# untitled.net
KiCad netlist of a schematic drawn in EAGLE
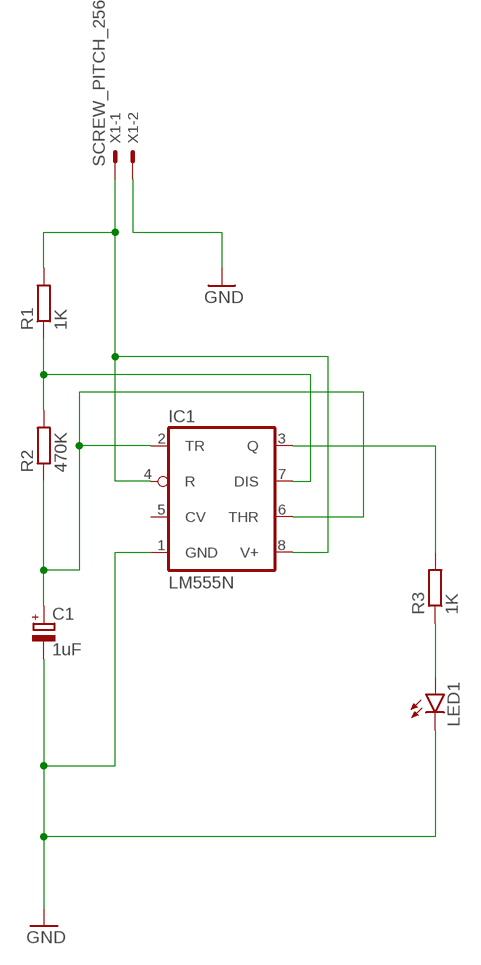
[diagram p0: schematic, sheet 1]

(export (version "E")
  (design (tool "Eeschema 10.0.6"))
  (components
    (comp (ref "C1")
      (value "1uF")
      (footprint "eagle-import:E2-5")
      (libsource (lib "eagle-import") (part "CPOL-EUE2-5"))
    )
    (comp (ref "IC1")
      (value "LM555N")
      (footprint "eagle-import:DIL08")
      (libsource (lib "eagle-import") (part "555NLM"))
    )
    (comp (ref "LED1")
      (value "LED_1206SMT1206")
      (footprint "eagle-import:1206")
      (libsource (lib "eagle-import") (part "LED_1206SMT1206"))
    )
    (comp (ref "R1")
      (value "1K")
      (footprint "eagle-import:0207_10")
      (libsource (lib "eagle-import") (part "CARBON/METAL_FILM_RESISTOR0207/10"))
    )
    (comp (ref "R2")
      (value "470K")
      (footprint "eagle-import:0207_10")
      (libsource (lib "eagle-import") (part "CARBON/METAL_FILM_RESISTOR0207/10"))
    )
    (comp (ref "R3")
      (value "1K")
      (footprint "eagle-import:0207_10")
      (libsource (lib "eagle-import") (part "CARBON/METAL_FILM_RESISTOR0207/10"))
    )
    (comp (ref "X1")
      (value "SCREW_PITCH_256")
      (footprint "eagle-import:22-23-2021")
      (fields (field (name "MF") "MOLEX") (field (name "MPN") "22-23-2021"))
      (libsource (lib "eagle-import") (part "SCREW_PITCH_256"))
    )
  )
  (nets
    (net (code "1") (name "GND") (class "Default")
      (node (ref "C1") (pin "-") (pinfunction "-_-") (pintype "passive"))
      (node (ref "IC1") (pin "1") (pinfunction "GND_1") (pintype "power_in"))
      (node (ref "LED1") (pin "C") (pinfunction "C_C") (pintype "passive"))
      (node (ref "X1") (pin "2") (pinfunction "S_2") (pintype "passive"))
    )
    (net (code "2") (name "Net-(IC1-DIS)") (class "Default")
      (node (ref "IC1") (pin "7") (pinfunction "DIS_7") (pintype "input"))
      (node (ref "R1") (pin "1") (pinfunction "1_1") (pintype "passive"))
      (node (ref "R2") (pin "2") (pinfunction "2_2") (pintype "passive"))
    )
    (net (code "3") (name "Net-(IC1-Q)") (class "Default")
      (node (ref "IC1") (pin "3") (pinfunction "Q_3") (pintype "output"))
      (node (ref "R3") (pin "2") (pinfunction "2_2") (pintype "passive"))
    )
    (net (code "4") (name "Net-(IC1-R)") (class "Default")
      (node (ref "IC1") (pin "4") (pinfunction "R_4") (pintype "input"))
      (node (ref "IC1") (pin "8") (pinfunction "V+_8") (pintype "power_in"))
      (node (ref "R1") (pin "2") (pinfunction "2_2") (pintype "passive"))
      (node (ref "X1") (pin "1") (pinfunction "S_1") (pintype "passive"))
    )
    (net (code "5") (name "Net-(IC1-THR)") (class "Default")
      (node (ref "C1") (pin "+") (pinfunction "+_+") (pintype "passive"))
      (node (ref "IC1") (pin "2") (pinfunction "TR_2") (pintype "input"))
      (node (ref "IC1") (pin "6") (pinfunction "THR_6") (pintype "input"))
      (node (ref "R2") (pin "1") (pinfunction "1_1") (pintype "passive"))
    )
    (net (code "6") (name "Net-(LED1-PadA)") (class "Default")
      (node (ref "LED1") (pin "A") (pinfunction "A_A") (pintype "passive"))
      (node (ref "R3") (pin "1") (pinfunction "1_1") (pintype "passive"))
    )
    (net (code "7") (name "unconnected-(IC1-CV-Pad5)") (class "Default")
      (node (ref "IC1") (pin "5") (pinfunction "CV_5") (pintype "input"))
    )
  )
)
